# PCB.net
KiCad netlist of a schematic drawn in Altium Designer
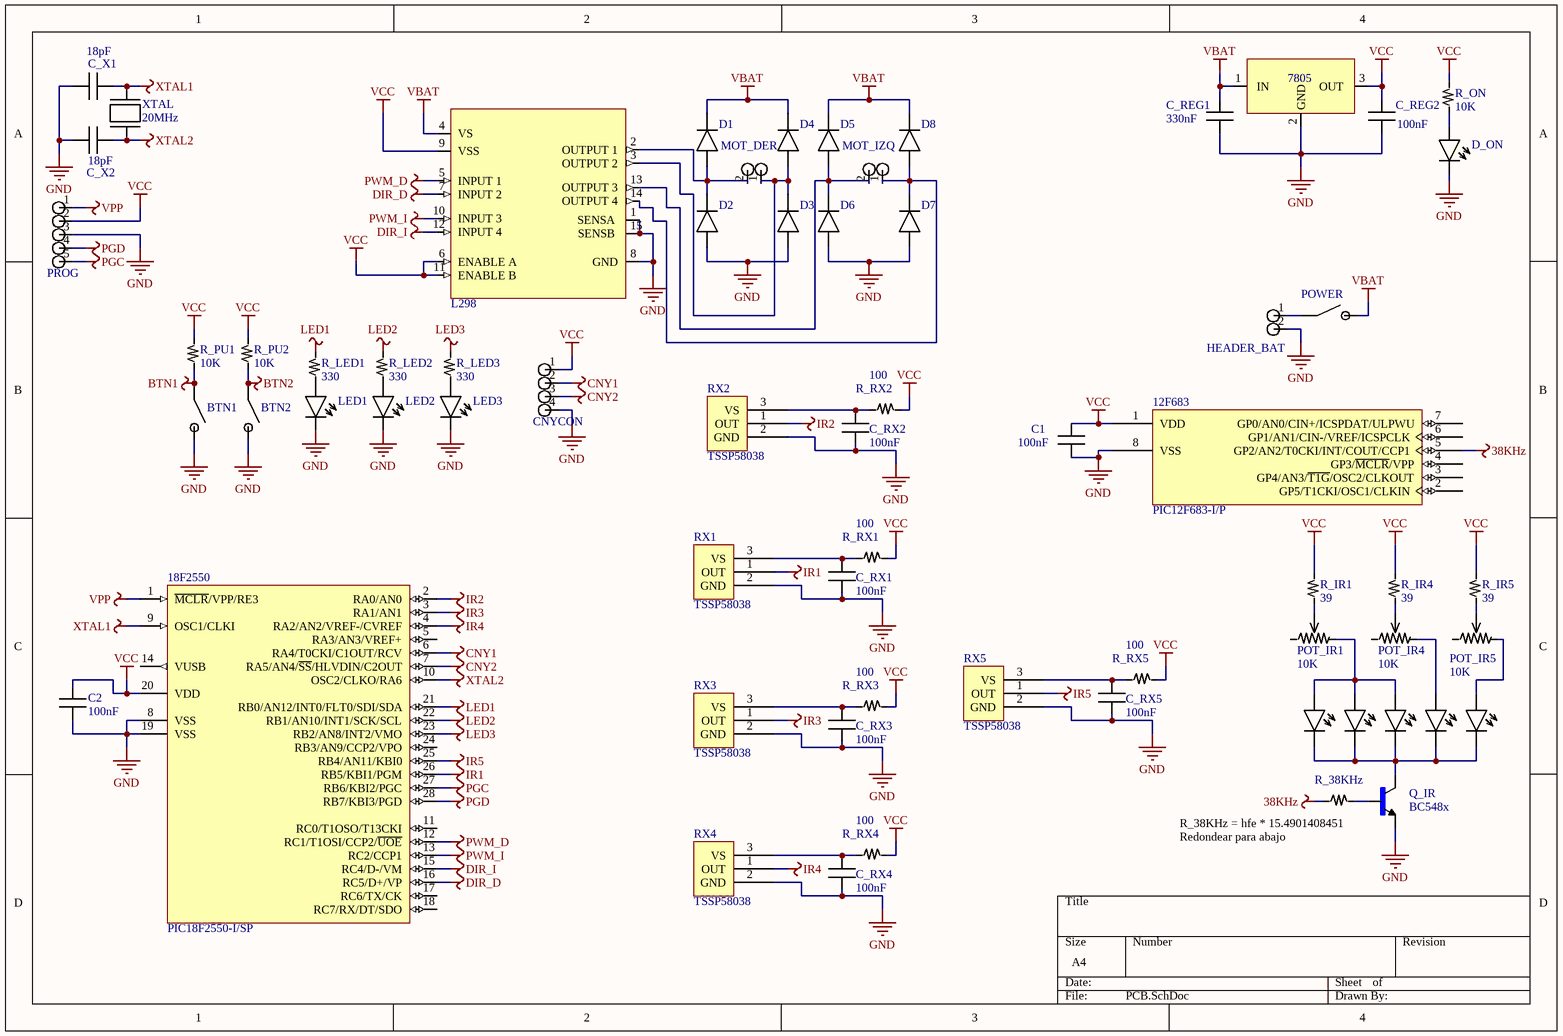
[diagram p0: PCB.SchDoc]

(export (version "E")
  (design (tool "Eeschema 10.0.6"))
  (components
    (comp (ref "12F683")
      (value "PIC12F683-I/P")
      (footprint "PDIP300-P8")
      (fields (field (name "PUBLISHER") "Altium Limited"))
      (libsource (lib "Microchip Microcontroller 8-Bit PIC12") (part "PIC12F683-I/P"))
    )
    (comp (ref "18F2550")
      (value "PIC18F2550-I/SP")
      (footprint "SPDIP300-SP28")
      (fields (field (name "PUBLISHER") "Altium Limited"))
      (libsource (lib "Microchip Microcontroller 8-Bit PIC18") (part "PIC18F2550-I/SP"))
    )
    (comp (ref "7805")
      (value "LM7805")
      (footprint "TO-220-STRAIGHT")
      (libsource (lib "Components") (part "LM7805"))
    )
    (comp (ref "BTN1")
      (value "SWITCH")
      (footprint "TACT_SWITCH-SMALL-4PIN")
      (libsource (lib "GlecerLib") (part "SWITCH"))
    )
    (comp (ref "BTN2")
      (value "SWITCH")
      (footprint "TACT_SWITCH-SMALL-4PIN")
      (libsource (lib "GlecerLib") (part "SWITCH"))
    )
    (comp (ref "C1")
      (value "100nF")
      (footprint "CAP-CER")
      (fields (field (name "Comment") "CAP-CER"))
      (libsource (lib "GlecerLib") (part "CAP-CER"))
    )
    (comp (ref "C2")
      (value "100nF")
      (footprint "CAP-CER")
      (fields (field (name "Comment") "CAP-CER"))
      (libsource (lib "GlecerLib") (part "CAP-CER"))
    )
    (comp (ref "CNYCON")
      (value "HEADER-4")
      (footprint "HEADER-4-VERTICAL")
      (libsource (lib "GlecerLib") (part "HEADER-4"))
    )
    (comp (ref "C_REG1")
      (value "330nF")
      (footprint "CAP-CER")
      (fields (field (name "Comment") "CAP-CER"))
      (libsource (lib "GlecerLib") (part "CAP-CER"))
    )
    (comp (ref "C_REG2")
      (value "100nF")
      (footprint "CAP-CER")
      (fields (field (name "Comment") "CAP-CER"))
      (libsource (lib "GlecerLib") (part "CAP-CER"))
    )
    (comp (ref "C_RX1")
      (value "100nF")
      (footprint "CAP-CER")
      (fields (field (name "Comment") "CAP-CER"))
      (libsource (lib "GlecerLib") (part "CAP-CER"))
    )
    (comp (ref "C_RX2")
      (value "100nF")
      (footprint "CAP-CER")
      (fields (field (name "Comment") "CAP-CER"))
      (libsource (lib "GlecerLib") (part "CAP-CER"))
    )
    (comp (ref "C_RX3")
      (value "100nF")
      (footprint "CAP-CER")
      (fields (field (name "Comment") "CAP-CER"))
      (libsource (lib "GlecerLib") (part "CAP-CER"))
    )
    (comp (ref "C_RX4")
      (value "100nF")
      (footprint "CAP-CER")
      (fields (field (name "Comment") "CAP-CER"))
      (libsource (lib "GlecerLib") (part "CAP-CER"))
    )
    (comp (ref "C_RX5")
      (value "100nF")
      (footprint "CAP-CER")
      (fields (field (name "Comment") "CAP-CER"))
      (libsource (lib "GlecerLib") (part "CAP-CER"))
    )
    (comp (ref "C_X1")
      (value "18pF")
      (footprint "CAP-CER")
      (fields (field (name "Comment") "CAP-CER"))
      (libsource (lib "Components") (part "CAP-CER"))
    )
    (comp (ref "C_X2")
      (value "18pF")
      (footprint "CAP-CER")
      (fields (field (name "Comment") "CAP-CER"))
      (libsource (lib "Components") (part "CAP-CER"))
    )
    (comp (ref "D1") (value "~") (footprint "DO-41") (libsource (lib "GlecerLib") (part "DIODE")))
    (comp (ref "D2") (value "~") (footprint "DO-41") (libsource (lib "GlecerLib") (part "DIODE")))
    (comp (ref "D3") (value "~") (footprint "DO-41") (libsource (lib "GlecerLib") (part "DIODE")))
    (comp (ref "D4") (value "~") (footprint "DO-41") (libsource (lib "GlecerLib") (part "DIODE")))
    (comp (ref "D5") (value "~") (footprint "DO-41") (libsource (lib "GlecerLib") (part "DIODE")))
    (comp (ref "D6") (value "~") (footprint "DO-41") (libsource (lib "GlecerLib") (part "DIODE")))
    (comp (ref "D7") (value "~") (footprint "DO-41") (libsource (lib "GlecerLib") (part "DIODE")))
    (comp (ref "D8") (value "~") (footprint "DO-41") (libsource (lib "GlecerLib") (part "DIODE")))
    (comp (ref "D_IR1") (value "LED") (footprint "LED-3MM-YELLOW") (libsource (lib "GlecerLib") (part "LED")))
    (comp (ref "D_IR2") (value "LED") (footprint "LED-3MM-YELLOW") (libsource (lib "GlecerLib") (part "LED")))
    (comp (ref "D_IR3") (value "LED") (footprint "LED-3MM-YELLOW") (libsource (lib "GlecerLib") (part "LED")))
    (comp (ref "D_IR4") (value "LED") (footprint "LED-3MM-YELLOW") (libsource (lib "GlecerLib") (part "LED")))
    (comp (ref "D_IR5") (value "LED") (footprint "LED-3MM-YELLOW") (libsource (lib "GlecerLib") (part "LED")))
    (comp (ref "D_ON") (value "LED") (footprint "LED-3MM-RED") (libsource (lib "Components") (part "LED")))
    (comp (ref "HEADER_BAT")
      (value "HEADER-2")
      (footprint "HEADER-2-VERTICAL")
      (libsource (lib "Components") (part "HEADER-2"))
    )
    (comp (ref "L298") (value "L298") (footprint "Multiwatt15") (libsource (lib "Components") (part "L298")))
    (comp (ref "LED1") (value "LED") (footprint "LED-3MM-RED") (libsource (lib "Components") (part "LED")))
    (comp (ref "LED2") (value "LED") (footprint "LED-3MM-RED") (libsource (lib "Components") (part "LED")))
    (comp (ref "LED3") (value "LED") (footprint "LED-3MM-RED") (libsource (lib "Components") (part "LED")))
    (comp (ref "MOT_DER")
      (value "HEADER-2")
      (footprint "HEADER-2-VERTICAL")
      (libsource (lib "GlecerLib") (part "HEADER-2"))
    )
    (comp (ref "MOT_IZQ")
      (value "HEADER-2")
      (footprint "HEADER-2-VERTICAL")
      (libsource (lib "GlecerLib") (part "HEADER-2"))
    )
    (comp (ref "POT_IR1") (value "10K") (footprint "MULTITURN") (libsource (lib "GlecerLib") (part "POT")))
    (comp (ref "POT_IR4") (value "10K") (footprint "MULTITURN") (libsource (lib "GlecerLib") (part "POT")))
    (comp (ref "POT_IR5") (value "10K") (footprint "MULTITURN") (libsource (lib "GlecerLib") (part "POT")))
    (comp (ref "POWER")
      (value "SWITCH")
      (footprint "ORT_SWITCH")
      (libsource (lib "GlecerLib") (part "SWITCH"))
    )
    (comp (ref "PROG")
      (value "HEADER-5")
      (footprint "HEADER-5-VERTICAL")
      (libsource (lib "GlecerLib") (part "HEADER-5"))
    )
    (comp (ref "Q_IR")
      (value "BC548x")
      (footprint "TO92-EBC_BC548*(Primary)")
      (description "Transistor Silicon Npn Ambient Rated To D3007, Bc5")
      (fields (field (name "MP") "BC548") (field (name "MF") "NXP Semiconductors"))
      (libsource (lib "BC548_") (part "BC548*"))
    )
    (comp (ref "RX1")
      (value "TSSP58038")
      (footprint "TSSP58038")
      (libsource (lib "GlecerLib") (part "TSSP58038"))
    )
    (comp (ref "RX2")
      (value "TSSP58038")
      (footprint "TSSP58038")
      (libsource (lib "GlecerLib") (part "TSSP58038"))
    )
    (comp (ref "RX3")
      (value "TSSP58038")
      (footprint "TSSP58038")
      (libsource (lib "GlecerLib") (part "TSSP58038"))
    )
    (comp (ref "RX4")
      (value "TSSP58038")
      (footprint "TSSP58038")
      (libsource (lib "GlecerLib") (part "TSSP58038"))
    )
    (comp (ref "RX5")
      (value "TSSP58038")
      (footprint "TSSP58038")
      (libsource (lib "GlecerLib") (part "TSSP58038"))
    )
    (comp (ref "R_38KHz")
      (value "RES")
      (footprint "RES-Axial-400mil")
      (libsource (lib "GlecerLib") (part "RES"))
    )
    (comp (ref "R_IR1")
      (value "39")
      (footprint "RES-Axial-400mil")
      (fields (field (name "Comment") "RES"))
      (libsource (lib "GlecerLib") (part "RES"))
    )
    (comp (ref "R_IR4")
      (value "39")
      (footprint "RES-Axial-400mil")
      (fields (field (name "Comment") "RES"))
      (libsource (lib "GlecerLib") (part "RES"))
    )
    (comp (ref "R_IR5")
      (value "39")
      (footprint "RES-Axial-400mil")
      (fields (field (name "Comment") "RES"))
      (libsource (lib "GlecerLib") (part "RES"))
    )
    (comp (ref "R_LED1")
      (value "330")
      (footprint "RES-Axial-400mil")
      (fields (field (name "Comment") "RES"))
      (libsource (lib "GlecerLib") (part "RES"))
    )
    (comp (ref "R_LED2")
      (value "330")
      (footprint "RES-Axial-400mil")
      (fields (field (name "Comment") "RES"))
      (libsource (lib "GlecerLib") (part "RES"))
    )
    (comp (ref "R_LED3")
      (value "330")
      (footprint "RES-Axial-400mil")
      (fields (field (name "Comment") "RES"))
      (libsource (lib "GlecerLib") (part "RES"))
    )
    (comp (ref "R_ON")
      (value "10K")
      (footprint "RES-Axial-400mil")
      (fields (field (name "Comment") "RES"))
      (libsource (lib "GlecerLib") (part "RES"))
    )
    (comp (ref "R_PU1")
      (value "10K")
      (footprint "RES-Axial-400mil")
      (fields (field (name "Comment") "RES"))
      (libsource (lib "GlecerLib") (part "RES"))
    )
    (comp (ref "R_PU2")
      (value "10K")
      (footprint "RES-Axial-400mil")
      (fields (field (name "Comment") "RES"))
      (libsource (lib "GlecerLib") (part "RES"))
    )
    (comp (ref "R_RX1")
      (value "100")
      (footprint "RES-Axial-400mil")
      (fields (field (name "Comment") "RES"))
      (libsource (lib "GlecerLib") (part "RES"))
    )
    (comp (ref "R_RX2")
      (value "100")
      (footprint "RES-Axial-400mil")
      (fields (field (name "Comment") "RES"))
      (libsource (lib "GlecerLib") (part "RES"))
    )
    (comp (ref "R_RX3")
      (value "100")
      (footprint "RES-Axial-400mil")
      (fields (field (name "Comment") "RES"))
      (libsource (lib "GlecerLib") (part "RES"))
    )
    (comp (ref "R_RX4")
      (value "100")
      (footprint "RES-Axial-400mil")
      (fields (field (name "Comment") "RES"))
      (libsource (lib "GlecerLib") (part "RES"))
    )
    (comp (ref "R_RX5")
      (value "100")
      (footprint "RES-Axial-400mil")
      (fields (field (name "Comment") "RES"))
      (libsource (lib "GlecerLib") (part "RES"))
    )
    (comp (ref "XTAL")
      (value "CRYSTAL-OSC")
      (footprint "HC-49/S")
      (fields (field (name "FREQUENCY") "20MHz"))
      (libsource (lib "Components") (part "CRYSTAL-OSC"))
    )
  )
  (nets
    (net (code "1") (name "38KHz") (class "Default")
      (node (ref "12F683") (pin "5") (pinfunction "GP2/AN2/T0CKI/INT/COUT/CCP1_5") (pintype "bidirectional"))
      (node (ref "R_38KHz") (pin "2") (pintype "passive"))
    )
    (net (code "2") (name "BTN1") (class "Default")
      (node (ref "BTN1") (pin "1") (pintype "passive"))
      (node (ref "R_PU1") (pin "2") (pintype "passive"))
    )
    (net (code "3") (name "BTN2") (class "Default")
      (node (ref "BTN2") (pin "1") (pintype "passive"))
      (node (ref "R_PU2") (pin "2") (pintype "passive"))
    )
    (net (code "4") (name "CNY1") (class "Default")
      (node (ref "18F2550") (pin "6") (pinfunction "RA4/T0CKI/C1OUT/RCV_6") (pintype "bidirectional"))
      (node (ref "CNYCON") (pin "2") (pintype "passive"))
    )
    (net (code "5") (name "CNY2") (class "Default")
      (node (ref "18F2550") (pin "7") (pinfunction "RA5/AN4/~{SS}/HLVDIN/C2OUT_7") (pintype "bidirectional"))
      (node (ref "CNYCON") (pin "3") (pintype "passive"))
    )
    (net (code "6") (name "DIR_D") (class "Default")
      (node (ref "18F2550") (pin "16") (pinfunction "RC5/D+/VP_16") (pintype "bidirectional"))
      (node (ref "L298") (pin "7") (pinfunction "INPUT_2_7") (pintype "input"))
    )
    (net (code "7") (name "DIR_I") (class "Default")
      (node (ref "18F2550") (pin "15") (pinfunction "RC4/D-/VM_15") (pintype "bidirectional"))
      (node (ref "L298") (pin "12") (pinfunction "INPUT_4_12") (pintype "input"))
    )
    (net (code "8") (name "GND") (class "Default")
      (node (ref "12F683") (pin "8") (pinfunction "VSS_8") (pintype "power_in"))
      (node (ref "18F2550") (pin "19") (pinfunction "VSS_19") (pintype "power_in"))
      (node (ref "18F2550") (pin "8") (pinfunction "VSS_8") (pintype "power_in"))
      (node (ref "7805") (pin "2") (pinfunction "GND_2") (pintype "power_in"))
      (node (ref "BTN1") (pin "2") (pintype "passive"))
      (node (ref "BTN2") (pin "2") (pintype "passive"))
      (node (ref "C1") (pin "1") (pintype "passive"))
      (node (ref "C2") (pin "1") (pintype "passive"))
      (node (ref "CNYCON") (pin "4") (pintype "passive"))
      (node (ref "C_REG1") (pin "1") (pintype "passive"))
      (node (ref "C_REG2") (pin "1") (pintype "passive"))
      (node (ref "C_RX1") (pin "2") (pintype "passive"))
      (node (ref "C_RX2") (pin "2") (pintype "passive"))
      (node (ref "C_RX3") (pin "2") (pintype "passive"))
      (node (ref "C_RX4") (pin "2") (pintype "passive"))
      (node (ref "C_RX5") (pin "2") (pintype "passive"))
      (node (ref "C_X1") (pin "1") (pintype "passive"))
      (node (ref "C_X2") (pin "1") (pintype "passive"))
      (node (ref "D2") (pin "A") (pintype "passive"))
      (node (ref "D3") (pin "A") (pintype "passive"))
      (node (ref "D6") (pin "A") (pintype "passive"))
      (node (ref "D7") (pin "A") (pintype "passive"))
      (node (ref "D_ON") (pin "K") (pintype "passive"))
      (node (ref "HEADER_BAT") (pin "2") (pintype "passive"))
      (node (ref "L298") (pin "1") (pinfunction "SENSA_1") (pintype "power_in"))
      (node (ref "L298") (pin "15") (pinfunction "SENSB_15") (pintype "power_in"))
      (node (ref "L298") (pin "8") (pinfunction "GND_8") (pintype "power_in"))
      (node (ref "LED1") (pin "K") (pintype "passive"))
      (node (ref "LED2") (pin "K") (pintype "passive"))
      (node (ref "LED3") (pin "K") (pintype "passive"))
      (node (ref "PROG") (pin "3") (pintype "passive"))
      (node (ref "Q_IR") (pin "E") (pinfunction "E_E") (pintype "passive"))
      (node (ref "RX1") (pin "2") (pinfunction "GND_2") (pintype "power_in"))
      (node (ref "RX2") (pin "2") (pinfunction "GND_2") (pintype "power_in"))
      (node (ref "RX3") (pin "2") (pinfunction "GND_2") (pintype "power_in"))
      (node (ref "RX4") (pin "2") (pinfunction "GND_2") (pintype "power_in"))
      (node (ref "RX5") (pin "2") (pinfunction "GND_2") (pintype "power_in"))
    )
    (net (code "9") (name "IR1") (class "Default")
      (node (ref "18F2550") (pin "26") (pinfunction "RB5/KBI1/PGM_26") (pintype "bidirectional"))
      (node (ref "RX1") (pin "1") (pinfunction "OUT_1") (pintype "power_in"))
    )
    (net (code "10") (name "IR2") (class "Default")
      (node (ref "18F2550") (pin "2") (pinfunction "RA0/AN0_2") (pintype "bidirectional"))
      (node (ref "RX2") (pin "1") (pinfunction "OUT_1") (pintype "power_in"))
    )
    (net (code "11") (name "IR3") (class "Default")
      (node (ref "18F2550") (pin "3") (pinfunction "RA1/AN1_3") (pintype "bidirectional"))
      (node (ref "RX3") (pin "1") (pinfunction "OUT_1") (pintype "power_in"))
    )
    (net (code "12") (name "IR4") (class "Default")
      (node (ref "18F2550") (pin "4") (pinfunction "RA2/AN2/VREF-/CVREF_4") (pintype "bidirectional"))
      (node (ref "RX4") (pin "1") (pinfunction "OUT_1") (pintype "power_in"))
    )
    (net (code "13") (name "IR5") (class "Default")
      (node (ref "18F2550") (pin "25") (pinfunction "RB4/AN11/KBI0_25") (pintype "bidirectional"))
      (node (ref "RX5") (pin "1") (pinfunction "OUT_1") (pintype "power_in"))
    )
    (net (code "14") (name "LED1") (class "Default")
      (node (ref "18F2550") (pin "21") (pinfunction "RB0/AN12/INT0/FLT0/SDI/SDA_21") (pintype "bidirectional"))
      (node (ref "R_LED1") (pin "1") (pintype "passive"))
    )
    (net (code "15") (name "LED2") (class "Default")
      (node (ref "18F2550") (pin "22") (pinfunction "RB1/AN10/INT1/SCK/SCL_22") (pintype "bidirectional"))
      (node (ref "R_LED2") (pin "1") (pintype "passive"))
    )
    (net (code "16") (name "LED3") (class "Default")
      (node (ref "18F2550") (pin "23") (pinfunction "RB2/AN8/INT2/VMO_23") (pintype "bidirectional"))
      (node (ref "R_LED3") (pin "1") (pintype "passive"))
    )
    (net (code "17") (name "Net-(D_IR1-PadA)") (class "Default")
      (node (ref "D_IR1") (pin "A") (pintype "passive"))
      (node (ref "D_IR2") (pin "A") (pintype "passive"))
      (node (ref "D_IR3") (pin "A") (pintype "passive"))
      (node (ref "POT_IR1") (pin "3") (pintype "passive"))
    )
    (net (code "18") (name "Net-(D_IR1-PadK)") (class "Default")
      (node (ref "D_IR1") (pin "K") (pintype "passive"))
      (node (ref "D_IR2") (pin "K") (pintype "passive"))
      (node (ref "D_IR3") (pin "K") (pintype "passive"))
      (node (ref "D_IR4") (pin "K") (pintype "passive"))
      (node (ref "D_IR5") (pin "K") (pintype "passive"))
      (node (ref "Q_IR") (pin "C") (pinfunction "C_C") (pintype "passive"))
    )
    (net (code "19") (name "Net-(D_IR4-PadA)") (class "Default")
      (node (ref "D_IR4") (pin "A") (pintype "passive"))
      (node (ref "POT_IR4") (pin "3") (pintype "passive"))
    )
    (net (code "20") (name "Net-(D_IR5-PadA)") (class "Default")
      (node (ref "D_IR5") (pin "A") (pintype "passive"))
      (node (ref "POT_IR5") (pin "3") (pintype "passive"))
    )
    (net (code "21") (name "Net-(D_ON-PadA)") (class "Default")
      (node (ref "D_ON") (pin "A") (pintype "passive"))
      (node (ref "R_ON") (pin "2") (pintype "passive"))
    )
    (net (code "22") (name "Net-(HEADER_BAT-Pad1)") (class "Default")
      (node (ref "HEADER_BAT") (pin "1") (pintype "passive"))
      (node (ref "POWER") (pin "1") (pintype "passive"))
    )
    (net (code "23") (name "Net-(L298-OUTPUT_1)") (class "Default")
      (node (ref "D1") (pin "A") (pintype "passive"))
      (node (ref "D2") (pin "K") (pintype "passive"))
      (node (ref "L298") (pin "2") (pinfunction "OUTPUT_1_2") (pintype "output"))
      (node (ref "MOT_DER") (pin "2") (pintype "passive"))
    )
    (net (code "24") (name "Net-(L298-OUTPUT_2)") (class "Default")
      (node (ref "D3") (pin "K") (pintype "passive"))
      (node (ref "D4") (pin "A") (pintype "passive"))
      (node (ref "L298") (pin "3") (pinfunction "OUTPUT_2_3") (pintype "output"))
      (node (ref "MOT_DER") (pin "1") (pintype "passive"))
    )
    (net (code "25") (name "Net-(L298-OUTPUT_3)") (class "Default")
      (node (ref "D5") (pin "A") (pintype "passive"))
      (node (ref "D6") (pin "K") (pintype "passive"))
      (node (ref "L298") (pin "13") (pinfunction "OUTPUT_3_13") (pintype "output"))
      (node (ref "MOT_IZQ") (pin "2") (pintype "passive"))
    )
    (net (code "26") (name "Net-(L298-OUTPUT_4)") (class "Default")
      (node (ref "D7") (pin "K") (pintype "passive"))
      (node (ref "D8") (pin "A") (pintype "passive"))
      (node (ref "L298") (pin "14") (pinfunction "OUTPUT_4_14") (pintype "output"))
      (node (ref "MOT_IZQ") (pin "1") (pintype "passive"))
    )
    (net (code "27") (name "Net-(LED1-PadA)") (class "Default")
      (node (ref "LED1") (pin "A") (pintype "passive"))
      (node (ref "R_LED1") (pin "2") (pintype "passive"))
    )
    (net (code "28") (name "Net-(LED2-PadA)") (class "Default")
      (node (ref "LED2") (pin "A") (pintype "passive"))
      (node (ref "R_LED2") (pin "2") (pintype "passive"))
    )
    (net (code "29") (name "Net-(LED3-PadA)") (class "Default")
      (node (ref "LED3") (pin "A") (pintype "passive"))
      (node (ref "R_LED3") (pin "2") (pintype "passive"))
    )
    (net (code "30") (name "Net-(POT_IR1-Pad2)") (class "Default")
      (node (ref "POT_IR1") (pin "2") (pintype "passive"))
      (node (ref "R_IR1") (pin "2") (pintype "passive"))
    )
    (net (code "31") (name "Net-(POT_IR4-Pad2)") (class "Default")
      (node (ref "POT_IR4") (pin "2") (pintype "passive"))
      (node (ref "R_IR4") (pin "2") (pintype "passive"))
    )
    (net (code "32") (name "Net-(POT_IR5-Pad2)") (class "Default")
      (node (ref "POT_IR5") (pin "2") (pintype "passive"))
      (node (ref "R_IR5") (pin "2") (pintype "passive"))
    )
    (net (code "33") (name "Net-(Q_IR-PadB)") (class "Default")
      (node (ref "Q_IR") (pin "B") (pinfunction "B_B") (pintype "passive"))
      (node (ref "R_38KHz") (pin "1") (pintype "passive"))
    )
    (net (code "34") (name "Net-(RX1-VS)") (class "Default")
      (node (ref "C_RX1") (pin "1") (pintype "passive"))
      (node (ref "RX1") (pin "3") (pinfunction "VS_3") (pintype "power_in"))
      (node (ref "R_RX1") (pin "2") (pintype "passive"))
    )
    (net (code "35") (name "Net-(RX2-VS)") (class "Default")
      (node (ref "C_RX2") (pin "1") (pintype "passive"))
      (node (ref "RX2") (pin "3") (pinfunction "VS_3") (pintype "power_in"))
      (node (ref "R_RX2") (pin "2") (pintype "passive"))
    )
    (net (code "36") (name "Net-(RX3-VS)") (class "Default")
      (node (ref "C_RX3") (pin "1") (pintype "passive"))
      (node (ref "RX3") (pin "3") (pinfunction "VS_3") (pintype "power_in"))
      (node (ref "R_RX3") (pin "2") (pintype "passive"))
    )
    (net (code "37") (name "Net-(RX4-VS)") (class "Default")
      (node (ref "C_RX4") (pin "1") (pintype "passive"))
      (node (ref "RX4") (pin "3") (pinfunction "VS_3") (pintype "power_in"))
      (node (ref "R_RX4") (pin "2") (pintype "passive"))
    )
    (net (code "38") (name "Net-(RX5-VS)") (class "Default")
      (node (ref "C_RX5") (pin "1") (pintype "passive"))
      (node (ref "RX5") (pin "3") (pinfunction "VS_3") (pintype "power_in"))
      (node (ref "R_RX5") (pin "2") (pintype "passive"))
    )
    (net (code "39") (name "PGC") (class "Default")
      (node (ref "18F2550") (pin "27") (pinfunction "RB6/KBI2/PGC_27") (pintype "bidirectional"))
      (node (ref "PROG") (pin "5") (pintype "passive"))
    )
    (net (code "40") (name "PGD") (class "Default")
      (node (ref "18F2550") (pin "28") (pinfunction "RB7/KBI3/PGD_28") (pintype "bidirectional"))
      (node (ref "PROG") (pin "4") (pintype "passive"))
    )
    (net (code "41") (name "PWM_D") (class "Default")
      (node (ref "18F2550") (pin "12") (pinfunction "RC1/T1OSI/CCP2/~{UOE}_12") (pintype "bidirectional"))
      (node (ref "L298") (pin "5") (pinfunction "INPUT_1_5") (pintype "input"))
    )
    (net (code "42") (name "PWM_I") (class "Default")
      (node (ref "18F2550") (pin "13") (pinfunction "RC2/CCP1_13") (pintype "bidirectional"))
      (node (ref "L298") (pin "10") (pinfunction "INPUT_3_10") (pintype "input"))
    )
    (net (code "43") (name "VBAT") (class "Default")
      (node (ref "7805") (pin "1") (pinfunction "IN_1") (pintype "power_in"))
      (node (ref "C_REG1") (pin "2") (pintype "passive"))
      (node (ref "D1") (pin "K") (pintype "passive"))
      (node (ref "D4") (pin "K") (pintype "passive"))
      (node (ref "D5") (pin "K") (pintype "passive"))
      (node (ref "D8") (pin "K") (pintype "passive"))
      (node (ref "L298") (pin "4") (pinfunction "VS_4") (pintype "power_in"))
      (node (ref "POWER") (pin "2") (pintype "passive"))
    )
    (net (code "44") (name "VCC") (class "Default")
      (node (ref "12F683") (pin "1") (pinfunction "VDD_1") (pintype "power_in"))
      (node (ref "18F2550") (pin "20") (pinfunction "VDD_20") (pintype "power_in"))
      (node (ref "7805") (pin "3") (pinfunction "OUT_3") (pintype "power_in"))
      (node (ref "C1") (pin "2") (pintype "passive"))
      (node (ref "C2") (pin "2") (pintype "passive"))
      (node (ref "CNYCON") (pin "1") (pintype "passive"))
      (node (ref "C_REG2") (pin "2") (pintype "passive"))
      (node (ref "L298") (pin "11") (pinfunction "ENABLE_B_11") (pintype "input"))
      (node (ref "L298") (pin "6") (pinfunction "ENABLE_A_6") (pintype "input"))
      (node (ref "L298") (pin "9") (pinfunction "VSS_9") (pintype "power_in"))
      (node (ref "PROG") (pin "2") (pintype "passive"))
      (node (ref "R_IR1") (pin "1") (pintype "passive"))
      (node (ref "R_IR4") (pin "1") (pintype "passive"))
      (node (ref "R_IR5") (pin "1") (pintype "passive"))
      (node (ref "R_ON") (pin "1") (pintype "passive"))
      (node (ref "R_PU1") (pin "1") (pintype "passive"))
      (node (ref "R_PU2") (pin "1") (pintype "passive"))
      (node (ref "R_RX1") (pin "1") (pintype "passive"))
      (node (ref "R_RX2") (pin "1") (pintype "passive"))
      (node (ref "R_RX3") (pin "1") (pintype "passive"))
      (node (ref "R_RX4") (pin "1") (pintype "passive"))
      (node (ref "R_RX5") (pin "1") (pintype "passive"))
    )
    (net (code "45") (name "VPP") (class "Default")
      (node (ref "18F2550") (pin "1") (pinfunction "~{MCLR}/VPP/RE3_1") (pintype "input"))
      (node (ref "PROG") (pin "1") (pintype "passive"))
    )
    (net (code "46") (name "XTAL1") (class "Default")
      (node (ref "18F2550") (pin "9") (pinfunction "OSC1/CLKI_9") (pintype "input"))
      (node (ref "C_X1") (pin "2") (pintype "passive"))
      (node (ref "XTAL") (pin "2") (pintype "passive"))
    )
    (net (code "47") (name "XTAL2") (class "Default")
      (node (ref "18F2550") (pin "10") (pinfunction "OSC2/CLKO/RA6_10") (pintype "bidirectional"))
      (node (ref "C_X2") (pin "2") (pintype "passive"))
      (node (ref "XTAL") (pin "1") (pintype "passive"))
    )
    (net (code "48") (name "unconnected-(12F683-GP0{slash}AN0{slash}CIN+{slash}ICSPDAT{slash}ULPWU-Pad7)") (class "Default")
      (node (ref "12F683") (pin "7") (pinfunction "GP0/AN0/CIN+/ICSPDAT/ULPWU_7") (pintype "bidirectional"))
    )
    (net (code "49") (name "unconnected-(12F683-GP1{slash}AN1{slash}CIN-{slash}VREF{slash}ICSPCLK-Pad6)") (class "Default")
      (node (ref "12F683") (pin "6") (pinfunction "GP1/AN1/CIN-/VREF/ICSPCLK_6") (pintype "bidirectional"))
    )
    (net (code "50") (name "unconnected-(12F683-GP3{slash}~{MCLR}{slash}VPP-Pad4)") (class "Default")
      (node (ref "12F683") (pin "4") (pinfunction "GP3/~{MCLR}/VPP_4") (pintype "bidirectional"))
    )
    (net (code "51") (name "unconnected-(12F683-GP4{slash}AN3{slash}~{T1G}{slash}OSC2{slash}CLKOUT-Pad3)") (class "Default")
      (node (ref "12F683") (pin "3") (pinfunction "GP4/AN3/~{T1G}/OSC2/CLKOUT_3") (pintype "bidirectional"))
    )
    (net (code "52") (name "unconnected-(12F683-GP5{slash}T1CKI{slash}OSC1{slash}CLKIN-Pad2)") (class "Default")
      (node (ref "12F683") (pin "2") (pinfunction "GP5/T1CKI/OSC1/CLKIN_2") (pintype "bidirectional"))
    )
    (net (code "53") (name "unconnected-(18F2550-RA3{slash}AN3{slash}VREF+-Pad5)") (class "Default")
      (node (ref "18F2550") (pin "5") (pinfunction "RA3/AN3/VREF+_5") (pintype "bidirectional"))
    )
    (net (code "54") (name "unconnected-(18F2550-RB3{slash}AN9{slash}CCP2{slash}VPO-Pad24)") (class "Default")
      (node (ref "18F2550") (pin "24") (pinfunction "RB3/AN9/CCP2/VPO_24") (pintype "bidirectional"))
    )
    (net (code "55") (name "unconnected-(18F2550-RC0{slash}T1OSO{slash}T13CKI-Pad11)") (class "Default")
      (node (ref "18F2550") (pin "11") (pinfunction "RC0/T1OSO/T13CKI_11") (pintype "bidirectional"))
    )
    (net (code "56") (name "unconnected-(18F2550-RC6{slash}TX{slash}CK-Pad17)") (class "Default")
      (node (ref "18F2550") (pin "17") (pinfunction "RC6/TX/CK_17") (pintype "bidirectional"))
    )
    (net (code "57") (name "unconnected-(18F2550-RC7{slash}RX{slash}DT{slash}SDO-Pad18)") (class "Default")
      (node (ref "18F2550") (pin "18") (pinfunction "RC7/RX/DT/SDO_18") (pintype "bidirectional"))
    )
    (net (code "58") (name "unconnected-(18F2550-VUSB-Pad14)") (class "Default")
      (node (ref "18F2550") (pin "14") (pinfunction "VUSB_14") (pintype "output"))
    )
    (net (code "59") (name "unconnected-(POT_IR1-Pad1)") (class "Default")
      (node (ref "POT_IR1") (pin "1") (pintype "passive"))
    )
    (net (code "60") (name "unconnected-(POT_IR4-Pad1)") (class "Default")
      (node (ref "POT_IR4") (pin "1") (pintype "passive"))
    )
    (net (code "61") (name "unconnected-(POT_IR5-Pad1)") (class "Default")
      (node (ref "POT_IR5") (pin "1") (pintype "passive"))
    )
  )
)
